# lumiled_driver.net
KiCad netlist of a schematic drawn in EAGLE
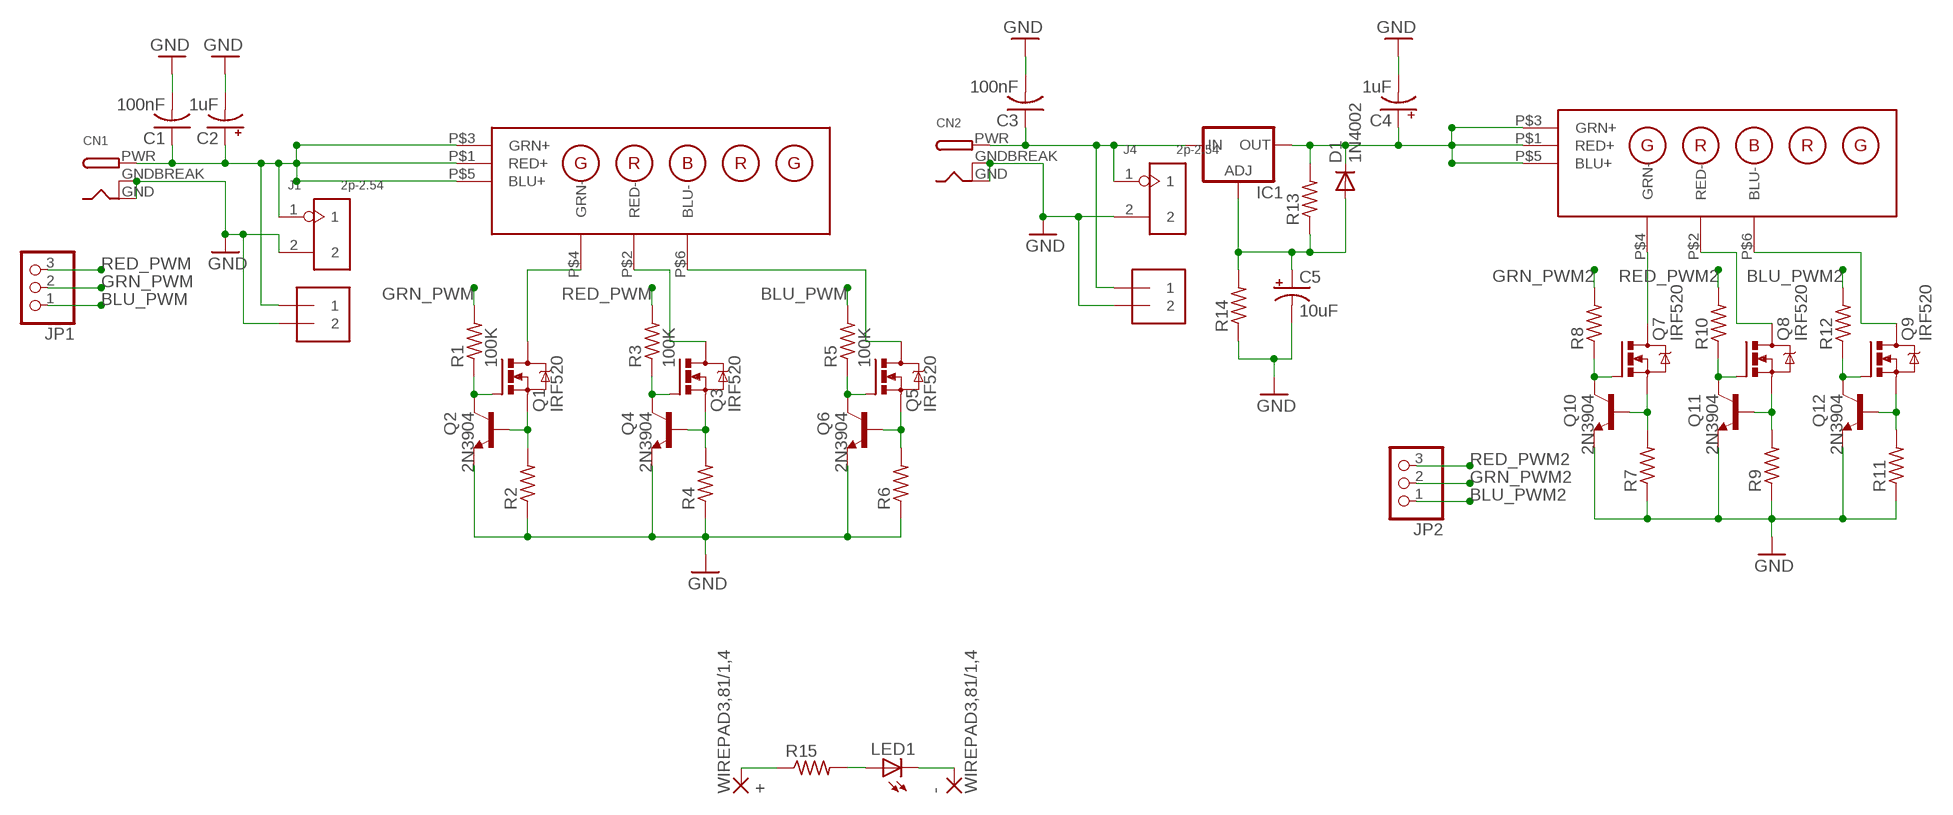
[diagram p0: schematic, sheet 1]

(export (version "E")
  (design (tool "Eeschema 10.0.6"))
  (components
    (comp (ref "+")
      (value "WIREPAD3,81/1,4")
      (footprint "eagle-import:3,81_1,4")
      (libsource (lib "eagle-import") (part "WIREPAD3,81/1,4"))
    )
    (comp (ref "-")
      (value "WIREPAD3,81/1,4")
      (footprint "eagle-import:3,81_1,4")
      (libsource (lib "eagle-import") (part "WIREPAD3,81/1,4"))
    )
    (comp (ref "C1")
      (value "100nF")
      (footprint "eagle-import:C025-024X044")
      (libsource (lib "eagle-import") (part "C-US025-024X044"))
    )
    (comp (ref "C2")
      (value "1uF")
      (footprint "eagle-import:TT2D5")
      (libsource (lib "eagle-import") (part "CPOL-USTT2D5"))
    )
    (comp (ref "C3")
      (value "100nF")
      (footprint "eagle-import:C025-024X044")
      (libsource (lib "eagle-import") (part "C-US025-024X044"))
    )
    (comp (ref "C4")
      (value "1uF")
      (footprint "eagle-import:TT2D5")
      (libsource (lib "eagle-import") (part "CPOL-USTT2D5"))
    )
    (comp (ref "C5")
      (value "10uF")
      (footprint "eagle-import:TT2D5")
      (libsource (lib "eagle-import") (part "CPOL-USTT2D5"))
    )
    (comp (ref "CN1")
      (value "DCBARRELPTH")
      (footprint "eagle-import:DCJACK_2MM_PTH")
      (libsource (lib "eagle-import") (part "DCBARRELPTH"))
    )
    (comp (ref "CN2")
      (value "DCBARRELPTH")
      (footprint "eagle-import:DCJACK_2MM_PTH")
      (libsource (lib "eagle-import") (part "DCBARRELPTH"))
    )
    (comp (ref "D1")
      (value "1N4002")
      (footprint "eagle-import:DO41-10")
      (libsource (lib "eagle-import") (part "1N4004"))
    )
    (comp (ref "IC1")
      (value "LM317TL")
      (footprint "eagle-import:317TL")
      (libsource (lib "eagle-import") (part "LM317TL"))
    )
    (comp (ref "J1")
      (value "2p-2.54")
      (footprint "eagle-import:H2-2.54")
      (fields (field (name "MPN") "P125-1102A0BS116A1"))
      (libsource (lib "eagle-import") (part "DIP-BLACK-MALE-HEADER-VERT(2P-2.54)"))
    )
    (comp (ref "J2")
      (value "1X2-3.5MM")
      (footprint "eagle-import:1X2-3.5MM")
      (libsource (lib "eagle-import") (part "1X2-3.5MM"))
    )
    (comp (ref "J3")
      (value "1X2-3.5MM")
      (footprint "eagle-import:1X2-3.5MM")
      (libsource (lib "eagle-import") (part "1X2-3.5MM"))
    )
    (comp (ref "J4")
      (value "2p-2.54")
      (footprint "eagle-import:H2-2.54")
      (fields (field (name "MPN") "P125-1102A0BS116A1"))
      (libsource (lib "eagle-import") (part "DIP-BLACK-MALE-HEADER-VERT(2P-2.54)"))
    )
    (comp (ref "JP1")
      (value "PINHD-1X3")
      (footprint "eagle-import:1X03")
      (libsource (lib "eagle-import") (part "PINHD-1X3"))
    )
    (comp (ref "JP2")
      (value "PINHD-1X3")
      (footprint "eagle-import:1X03")
      (libsource (lib "eagle-import") (part "PINHD-1X3"))
    )
    (comp (ref "LED1")
      (value "LED3MM")
      (footprint "eagle-import:LED3MM")
      (libsource (lib "eagle-import") (part "LED3MM"))
    )
    (comp (ref "Q1")
      (value "IRF520")
      (footprint "eagle-import:TO220BV")
      (libsource (lib "eagle-import") (part "IRF520"))
    )
    (comp (ref "Q2")
      (value "2N3904")
      (footprint "eagle-import:TO92")
      (libsource (lib "eagle-import") (part "2N3904"))
    )
    (comp (ref "Q3")
      (value "IRF520")
      (footprint "eagle-import:TO220BV")
      (libsource (lib "eagle-import") (part "IRF520"))
    )
    (comp (ref "Q4")
      (value "2N3904")
      (footprint "eagle-import:TO92")
      (libsource (lib "eagle-import") (part "2N3904"))
    )
    (comp (ref "Q5")
      (value "IRF520")
      (footprint "eagle-import:TO220BV")
      (libsource (lib "eagle-import") (part "IRF520"))
    )
    (comp (ref "Q6")
      (value "2N3904")
      (footprint "eagle-import:TO92")
      (libsource (lib "eagle-import") (part "2N3904"))
    )
    (comp (ref "Q7")
      (value "IRF520")
      (footprint "eagle-import:TO220BV")
      (libsource (lib "eagle-import") (part "IRF520"))
    )
    (comp (ref "Q8")
      (value "IRF520")
      (footprint "eagle-import:TO220BV")
      (libsource (lib "eagle-import") (part "IRF520"))
    )
    (comp (ref "Q9")
      (value "IRF520")
      (footprint "eagle-import:TO220BV")
      (libsource (lib "eagle-import") (part "IRF520"))
    )
    (comp (ref "Q10")
      (value "2N3904")
      (footprint "eagle-import:TO92")
      (libsource (lib "eagle-import") (part "2N3904"))
    )
    (comp (ref "Q11")
      (value "2N3904")
      (footprint "eagle-import:TO92")
      (libsource (lib "eagle-import") (part "2N3904"))
    )
    (comp (ref "Q12")
      (value "2N3904")
      (footprint "eagle-import:TO92")
      (libsource (lib "eagle-import") (part "2N3904"))
    )
    (comp (ref "R1")
      (value "100K")
      (footprint "eagle-import:0411_12")
      (libsource (lib "eagle-import") (part "R-US_0411/12"))
    )
    (comp (ref "R2")
      (value "R-US_0411/12")
      (footprint "eagle-import:0411_12")
      (libsource (lib "eagle-import") (part "R-US_0411/12"))
    )
    (comp (ref "R3")
      (value "100K")
      (footprint "eagle-import:0411_12")
      (libsource (lib "eagle-import") (part "R-US_0411/12"))
    )
    (comp (ref "R4")
      (value "R-US_0411/12")
      (footprint "eagle-import:0411_12")
      (libsource (lib "eagle-import") (part "R-US_0411/12"))
    )
    (comp (ref "R5")
      (value "100K")
      (footprint "eagle-import:0411_12")
      (libsource (lib "eagle-import") (part "R-US_0411/12"))
    )
    (comp (ref "R6")
      (value "R-US_0411/12")
      (footprint "eagle-import:0411_12")
      (libsource (lib "eagle-import") (part "R-US_0411/12"))
    )
    (comp (ref "R7")
      (value "R-US_0411/12")
      (footprint "eagle-import:0411_12")
      (libsource (lib "eagle-import") (part "R-US_0411/12"))
    )
    (comp (ref "R8")
      (value "R-US_0411/12")
      (footprint "eagle-import:0411_12")
      (libsource (lib "eagle-import") (part "R-US_0411/12"))
    )
    (comp (ref "R9")
      (value "R-US_0411/12")
      (footprint "eagle-import:0411_12")
      (libsource (lib "eagle-import") (part "R-US_0411/12"))
    )
    (comp (ref "R10")
      (value "R-US_0411/12")
      (footprint "eagle-import:0411_12")
      (libsource (lib "eagle-import") (part "R-US_0411/12"))
    )
    (comp (ref "R11")
      (value "R-US_0411/12")
      (footprint "eagle-import:0411_12")
      (libsource (lib "eagle-import") (part "R-US_0411/12"))
    )
    (comp (ref "R12")
      (value "R-US_0411/12")
      (footprint "eagle-import:0411_12")
      (libsource (lib "eagle-import") (part "R-US_0411/12"))
    )
    (comp (ref "R13")
      (value "R-US_0411/12")
      (footprint "eagle-import:0411_12")
      (libsource (lib "eagle-import") (part "R-US_0411/12"))
    )
    (comp (ref "R14")
      (value "R-US_0411/12")
      (footprint "eagle-import:0411_12")
      (libsource (lib "eagle-import") (part "R-US_0411/12"))
    )
    (comp (ref "R15")
      (value "R-US_0207/12")
      (footprint "eagle-import:0207_12")
      (libsource (lib "eagle-import") (part "R-US_0207/12"))
    )
    (comp (ref "U$1")
      (value "LUMILED_PARALLEL")
      (footprint "eagle-import:LED_PAR")
      (libsource (lib "eagle-import") (part "LUMILED_PARALLEL"))
    )
    (comp (ref "U$2")
      (value "LUMILED_PARALLEL")
      (footprint "eagle-import:LED_PAR")
      (libsource (lib "eagle-import") (part "LUMILED_PARALLEL"))
    )
  )
  (nets
    (net (code "1") (name "/BLU_PWM") (class "Default")
      (node (ref "JP1") (pin "1") (pinfunction "1_1") (pintype "passive"))
      (node (ref "R5") (pin "2") (pinfunction "2_2") (pintype "passive"))
    )
    (net (code "2") (name "/BLU_PWM2") (class "Default")
      (node (ref "JP2") (pin "1") (pinfunction "1_1") (pintype "passive"))
      (node (ref "R12") (pin "2") (pinfunction "2_2") (pintype "passive"))
    )
    (net (code "3") (name "/GRN_PWM") (class "Default")
      (node (ref "JP1") (pin "2") (pinfunction "2_2") (pintype "passive"))
      (node (ref "R1") (pin "2") (pinfunction "2_2") (pintype "passive"))
    )
    (net (code "4") (name "/GRN_PWM2") (class "Default")
      (node (ref "JP2") (pin "2") (pinfunction "2_2") (pintype "passive"))
      (node (ref "R8") (pin "2") (pinfunction "2_2") (pintype "passive"))
    )
    (net (code "5") (name "/RED_PWM") (class "Default")
      (node (ref "JP1") (pin "3") (pinfunction "3_3") (pintype "passive"))
      (node (ref "R3") (pin "2") (pinfunction "2_2") (pintype "passive"))
    )
    (net (code "6") (name "/RED_PWM2") (class "Default")
      (node (ref "JP2") (pin "3") (pinfunction "3_3") (pintype "passive"))
      (node (ref "R10") (pin "2") (pinfunction "2_2") (pintype "passive"))
    )
    (net (code "7") (name "GND") (class "Default")
      (node (ref "C1") (pin "2") (pinfunction "2_2") (pintype "passive"))
      (node (ref "C2") (pin "-") (pinfunction "-_-") (pintype "passive"))
      (node (ref "C3") (pin "2") (pinfunction "2_2") (pintype "passive"))
      (node (ref "C4") (pin "-") (pinfunction "-_-") (pintype "passive"))
      (node (ref "C5") (pin "-") (pinfunction "-_-") (pintype "passive"))
      (node (ref "CN1") (pin "GND") (pinfunction "GND_GND") (pintype "power_in"))
      (node (ref "CN1") (pin "GNDBREAK") (pinfunction "GNDBREAK_GNDBREAK") (pintype "power_in"))
      (node (ref "CN2") (pin "GND") (pinfunction "GND_GND") (pintype "power_in"))
      (node (ref "CN2") (pin "GNDBREAK") (pinfunction "GNDBREAK_GNDBREAK") (pintype "power_in"))
      (node (ref "J1") (pin "2") (pinfunction "2_2") (pintype "bidirectional"))
      (node (ref "J2") (pin "2") (pinfunction "2_2") (pintype "passive"))
      (node (ref "J3") (pin "2") (pinfunction "2_2") (pintype "passive"))
      (node (ref "J4") (pin "2") (pinfunction "2_2") (pintype "bidirectional"))
      (node (ref "Q10") (pin "3") (pinfunction "E_3") (pintype "passive"))
      (node (ref "Q11") (pin "3") (pinfunction "E_3") (pintype "passive"))
      (node (ref "Q12") (pin "3") (pinfunction "E_3") (pintype "passive"))
      (node (ref "Q2") (pin "3") (pinfunction "E_3") (pintype "passive"))
      (node (ref "Q4") (pin "3") (pinfunction "E_3") (pintype "passive"))
      (node (ref "Q6") (pin "3") (pinfunction "E_3") (pintype "passive"))
      (node (ref "R11") (pin "1") (pinfunction "1_1") (pintype "passive"))
      (node (ref "R14") (pin "1") (pinfunction "1_1") (pintype "passive"))
      (node (ref "R2") (pin "1") (pinfunction "1_1") (pintype "passive"))
      (node (ref "R4") (pin "1") (pinfunction "1_1") (pintype "passive"))
      (node (ref "R6") (pin "1") (pinfunction "1_1") (pintype "passive"))
      (node (ref "R7") (pin "1") (pinfunction "1_1") (pintype "passive"))
      (node (ref "R9") (pin "1") (pinfunction "1_1") (pintype "passive"))
    )
    (net (code "8") (name "Net-(+-P)") (class "Default")
      (node (ref "+") (pin "1") (pinfunction "P_1") (pintype "passive"))
      (node (ref "R15") (pin "1") (pinfunction "1_1") (pintype "passive"))
    )
    (net (code "9") (name "Net-(--P)") (class "Default")
      (node (ref "-") (pin "1") (pinfunction "P_1") (pintype "passive"))
      (node (ref "LED1") (pin "K") (pinfunction "C_K") (pintype "passive"))
    )
    (net (code "10") (name "Net-(IC1-ADJ)") (class "Default")
      (node (ref "C5") (pin "+") (pinfunction "+_+") (pintype "passive"))
      (node (ref "D1") (pin "A") (pinfunction "A_A") (pintype "passive"))
      (node (ref "IC1") (pin "1") (pinfunction "ADJ_1") (pintype "input"))
      (node (ref "R13") (pin "1") (pinfunction "1_1") (pintype "passive"))
      (node (ref "R14") (pin "2") (pinfunction "2_2") (pintype "passive"))
    )
    (net (code "11") (name "Net-(IC1-IN)") (class "Default")
      (node (ref "C3") (pin "1") (pinfunction "1_1") (pintype "passive"))
      (node (ref "CN2") (pin "PWR") (pinfunction "PWR_PWR") (pintype "power_in"))
      (node (ref "IC1") (pin "3") (pinfunction "IN_3") (pintype "input"))
      (node (ref "J3") (pin "1") (pinfunction "1_1") (pintype "passive"))
      (node (ref "J4") (pin "1") (pinfunction "1_1") (pintype "bidirectional"))
    )
    (net (code "12") (name "Net-(IC1-OUT)") (class "Default")
      (node (ref "C4") (pin "+") (pinfunction "+_+") (pintype "passive"))
      (node (ref "D1") (pin "C") (pinfunction "C_C") (pintype "passive"))
      (node (ref "IC1") (pin "2") (pinfunction "OUT_2") (pintype "passive"))
      (node (ref "R13") (pin "2") (pinfunction "2_2") (pintype "passive"))
      (node (ref "U$2") (pin "P$1") (pinfunction "RED+_P$1") (pintype "bidirectional"))
      (node (ref "U$2") (pin "P$3") (pinfunction "GRN+_P$3") (pintype "bidirectional"))
      (node (ref "U$2") (pin "P$5") (pinfunction "BLU+_P$5") (pintype "bidirectional"))
    )
    (net (code "13") (name "Net-(LED1-PadA)") (class "Default")
      (node (ref "LED1") (pin "A") (pinfunction "A_A") (pintype "passive"))
      (node (ref "R15") (pin "2") (pinfunction "2_2") (pintype "passive"))
    )
    (net (code "14") (name "Net-(Q2-B)") (class "Default")
      (node (ref "Q1") (pin "S") (pinfunction "S_S") (pintype "passive"))
      (node (ref "Q2") (pin "2") (pinfunction "B_2") (pintype "passive"))
      (node (ref "R2") (pin "2") (pinfunction "2_2") (pintype "passive"))
    )
    (net (code "15") (name "Net-(Q2-C)") (class "Default")
      (node (ref "Q1") (pin "G") (pinfunction "G_G") (pintype "passive"))
      (node (ref "Q2") (pin "1") (pinfunction "C_1") (pintype "passive"))
      (node (ref "R1") (pin "1") (pinfunction "1_1") (pintype "passive"))
    )
    (net (code "16") (name "Net-(Q4-B)") (class "Default")
      (node (ref "Q3") (pin "S") (pinfunction "S_S") (pintype "passive"))
      (node (ref "Q4") (pin "2") (pinfunction "B_2") (pintype "passive"))
      (node (ref "R4") (pin "2") (pinfunction "2_2") (pintype "passive"))
    )
    (net (code "17") (name "Net-(Q4-C)") (class "Default")
      (node (ref "Q3") (pin "G") (pinfunction "G_G") (pintype "passive"))
      (node (ref "Q4") (pin "1") (pinfunction "C_1") (pintype "passive"))
      (node (ref "R3") (pin "1") (pinfunction "1_1") (pintype "passive"))
    )
    (net (code "18") (name "Net-(Q6-B)") (class "Default")
      (node (ref "Q5") (pin "S") (pinfunction "S_S") (pintype "passive"))
      (node (ref "Q6") (pin "2") (pinfunction "B_2") (pintype "passive"))
      (node (ref "R6") (pin "2") (pinfunction "2_2") (pintype "passive"))
    )
    (net (code "19") (name "Net-(Q6-C)") (class "Default")
      (node (ref "Q5") (pin "G") (pinfunction "G_G") (pintype "passive"))
      (node (ref "Q6") (pin "1") (pinfunction "C_1") (pintype "passive"))
      (node (ref "R5") (pin "1") (pinfunction "1_1") (pintype "passive"))
    )
    (net (code "20") (name "Net-(Q10-B)") (class "Default")
      (node (ref "Q10") (pin "2") (pinfunction "B_2") (pintype "passive"))
      (node (ref "Q7") (pin "S") (pinfunction "S_S") (pintype "passive"))
      (node (ref "R7") (pin "2") (pinfunction "2_2") (pintype "passive"))
    )
    (net (code "21") (name "Net-(Q10-C)") (class "Default")
      (node (ref "Q10") (pin "1") (pinfunction "C_1") (pintype "passive"))
      (node (ref "Q7") (pin "G") (pinfunction "G_G") (pintype "passive"))
      (node (ref "R8") (pin "1") (pinfunction "1_1") (pintype "passive"))
    )
    (net (code "22") (name "Net-(Q11-B)") (class "Default")
      (node (ref "Q11") (pin "2") (pinfunction "B_2") (pintype "passive"))
      (node (ref "Q8") (pin "S") (pinfunction "S_S") (pintype "passive"))
      (node (ref "R9") (pin "2") (pinfunction "2_2") (pintype "passive"))
    )
    (net (code "23") (name "Net-(Q11-C)") (class "Default")
      (node (ref "Q11") (pin "1") (pinfunction "C_1") (pintype "passive"))
      (node (ref "Q8") (pin "G") (pinfunction "G_G") (pintype "passive"))
      (node (ref "R10") (pin "1") (pinfunction "1_1") (pintype "passive"))
    )
    (net (code "24") (name "Net-(Q12-B)") (class "Default")
      (node (ref "Q12") (pin "2") (pinfunction "B_2") (pintype "passive"))
      (node (ref "Q9") (pin "S") (pinfunction "S_S") (pintype "passive"))
      (node (ref "R11") (pin "2") (pinfunction "2_2") (pintype "passive"))
    )
    (net (code "25") (name "Net-(Q12-C)") (class "Default")
      (node (ref "Q12") (pin "1") (pinfunction "C_1") (pintype "passive"))
      (node (ref "Q9") (pin "G") (pinfunction "G_G") (pintype "passive"))
      (node (ref "R12") (pin "1") (pinfunction "1_1") (pintype "passive"))
    )
    (net (code "26") (name "Net-(U$1-BLU+)") (class "Default")
      (node (ref "C1") (pin "1") (pinfunction "1_1") (pintype "passive"))
      (node (ref "C2") (pin "+") (pinfunction "+_+") (pintype "passive"))
      (node (ref "CN1") (pin "PWR") (pinfunction "PWR_PWR") (pintype "power_in"))
      (node (ref "J1") (pin "1") (pinfunction "1_1") (pintype "bidirectional"))
      (node (ref "J2") (pin "1") (pinfunction "1_1") (pintype "passive"))
      (node (ref "U$1") (pin "P$1") (pinfunction "RED+_P$1") (pintype "bidirectional"))
      (node (ref "U$1") (pin "P$3") (pinfunction "GRN+_P$3") (pintype "bidirectional"))
      (node (ref "U$1") (pin "P$5") (pinfunction "BLU+_P$5") (pintype "bidirectional"))
    )
    (net (code "27") (name "Net-(U$1-BLU-)") (class "Default")
      (node (ref "Q5") (pin "D") (pinfunction "D_D") (pintype "passive"))
      (node (ref "U$1") (pin "P$6") (pinfunction "BLU-_P$6") (pintype "bidirectional"))
    )
    (net (code "28") (name "Net-(U$1-GRN-)") (class "Default")
      (node (ref "Q1") (pin "D") (pinfunction "D_D") (pintype "passive"))
      (node (ref "U$1") (pin "P$4") (pinfunction "GRN-_P$4") (pintype "bidirectional"))
    )
    (net (code "29") (name "Net-(U$1-RED-)") (class "Default")
      (node (ref "Q3") (pin "D") (pinfunction "D_D") (pintype "passive"))
      (node (ref "U$1") (pin "P$2") (pinfunction "RED-_P$2") (pintype "bidirectional"))
    )
    (net (code "30") (name "Net-(U$2-BLU-)") (class "Default")
      (node (ref "Q9") (pin "D") (pinfunction "D_D") (pintype "passive"))
      (node (ref "U$2") (pin "P$6") (pinfunction "BLU-_P$6") (pintype "bidirectional"))
    )
    (net (code "31") (name "Net-(U$2-GRN-)") (class "Default")
      (node (ref "Q7") (pin "D") (pinfunction "D_D") (pintype "passive"))
      (node (ref "U$2") (pin "P$4") (pinfunction "GRN-_P$4") (pintype "bidirectional"))
    )
    (net (code "32") (name "Net-(U$2-RED-)") (class "Default")
      (node (ref "Q8") (pin "D") (pinfunction "D_D") (pintype "passive"))
      (node (ref "U$2") (pin "P$2") (pinfunction "RED-_P$2") (pintype "bidirectional"))
    )
  )
)
